# uc2950.net
KiCad netlist of a schematic drawn in EAGLE
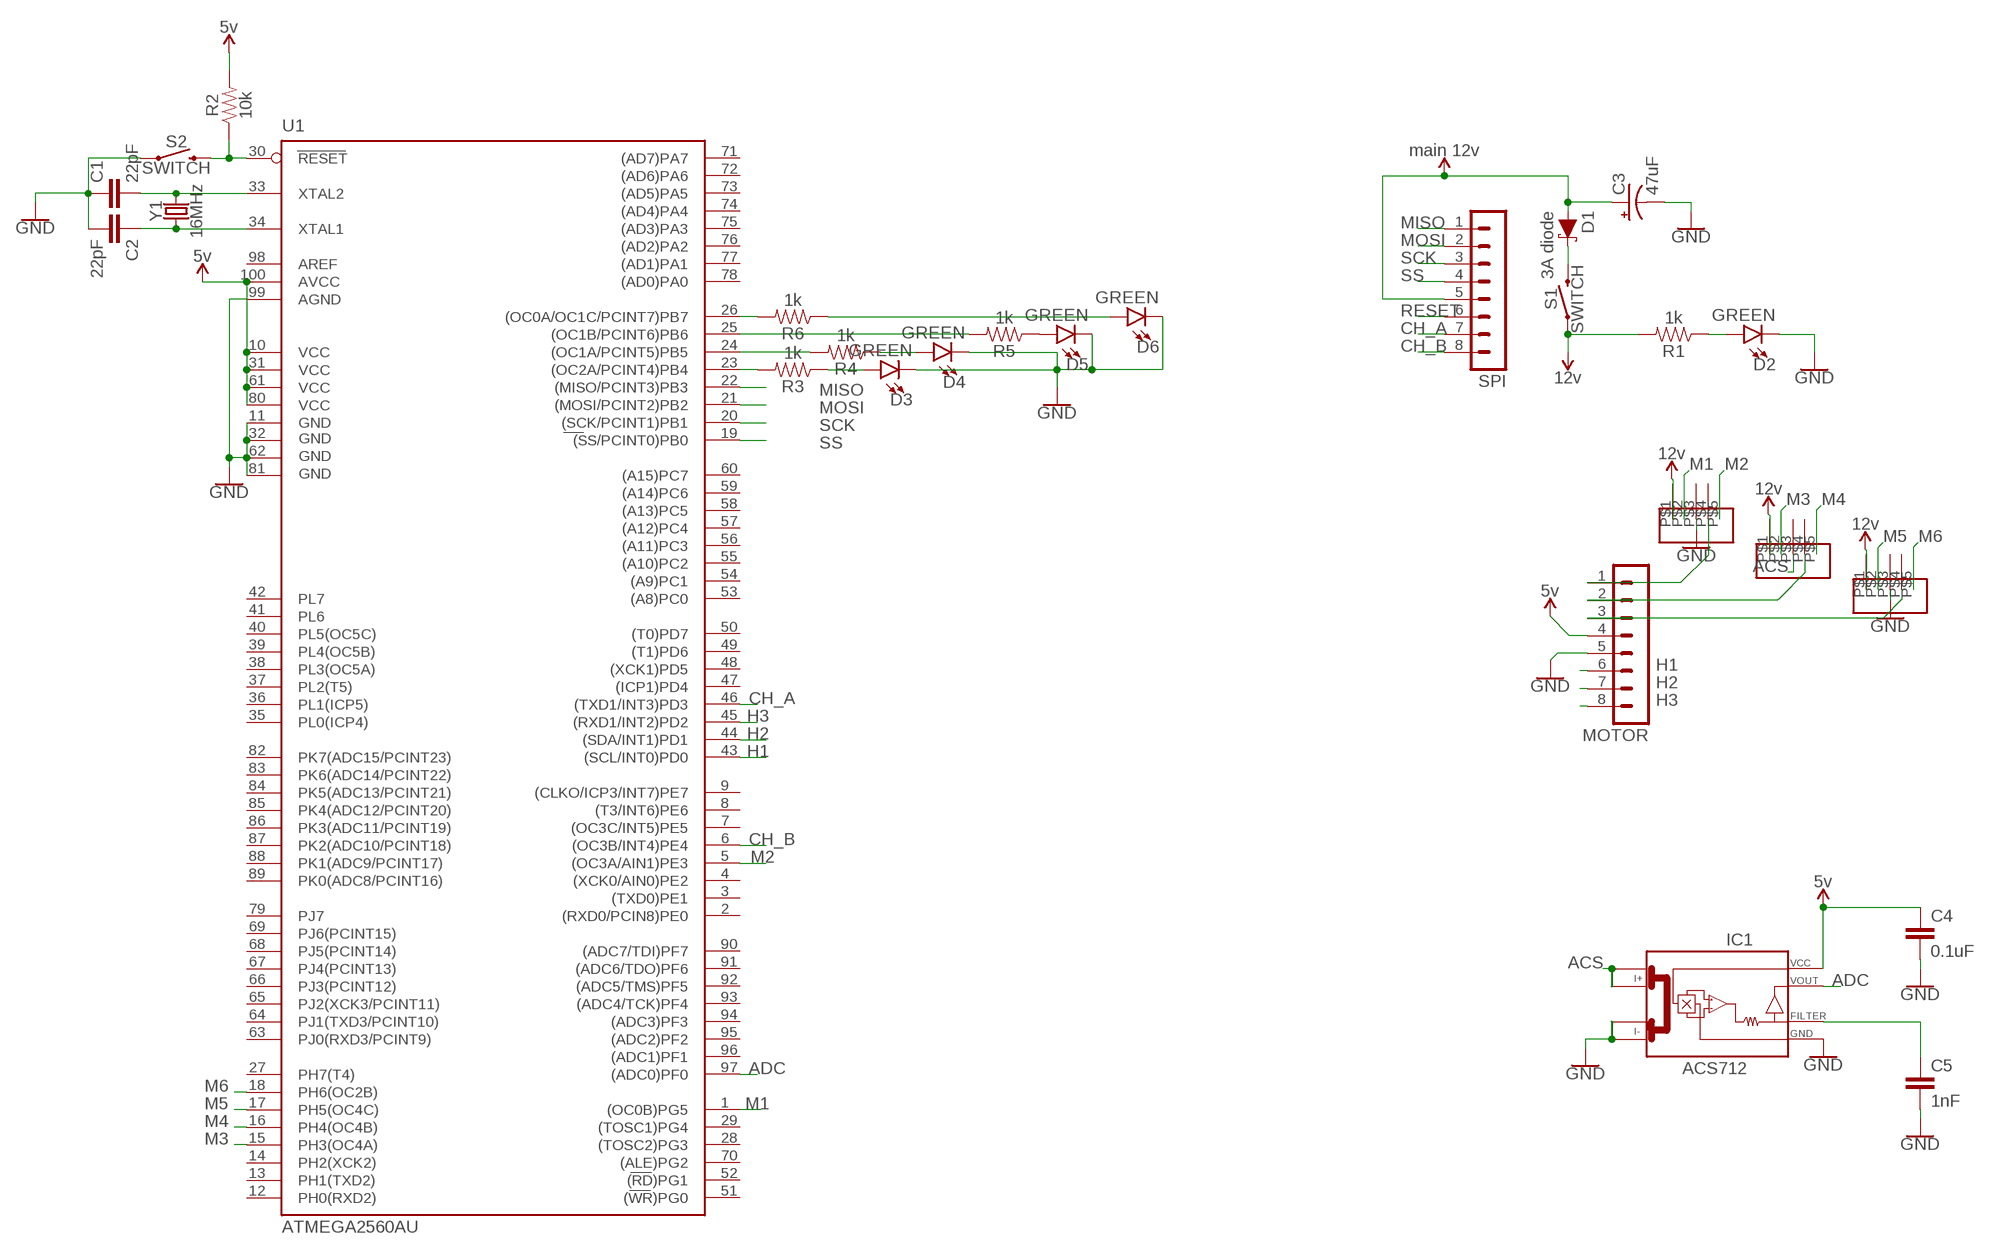
[diagram p0: schematic, sheet 1]

(export (version "E")
  (design (tool "Eeschema 10.0.6"))
  (components
    (comp (ref "C1")
      (value "22pF")
      (footprint "eagle-import:0603")
      (libsource (lib "eagle-import") (part "22PF-0603-50V-5%"))
    )
    (comp (ref "C2")
      (value "22pF")
      (footprint "eagle-import:0603")
      (libsource (lib "eagle-import") (part "22PF-0603-50V-5%"))
    )
    (comp (ref "C3")
      (value "47uF")
      (footprint "eagle-import:EIA3528")
      (libsource (lib "eagle-import") (part "47UF-POLAR-EIA3528-10V-10%"))
    )
    (comp (ref "C4")
      (value "0.1uF")
      (footprint "eagle-import:0603")
      (libsource (lib "eagle-import") (part "0.1UF-0603-25V-(+80/-20%)"))
    )
    (comp (ref "C5")
      (value "1nF")
      (footprint "eagle-import:0603")
      (libsource (lib "eagle-import") (part "1.0NF/1000PF-0603-50V-10%"))
    )
    (comp (ref "D1")
      (value "3A diode")
      (footprint "eagle-import:SMA-DIODE")
      (libsource (lib "eagle-import") (part "DIODE-SCHOTTKY-B340A"))
    )
    (comp (ref "D2")
      (value "GREEN")
      (footprint "eagle-import:LED-0603")
      (libsource (lib "eagle-import") (part "LED-GREEN0603"))
    )
    (comp (ref "D3")
      (value "GREEN")
      (footprint "eagle-import:LED-0603")
      (libsource (lib "eagle-import") (part "LED-GREEN0603"))
    )
    (comp (ref "D4")
      (value "GREEN")
      (footprint "eagle-import:LED-0603")
      (libsource (lib "eagle-import") (part "LED-GREEN0603"))
    )
    (comp (ref "D5")
      (value "GREEN")
      (footprint "eagle-import:LED-0603")
      (libsource (lib "eagle-import") (part "LED-GREEN0603"))
    )
    (comp (ref "D6")
      (value "GREEN")
      (footprint "eagle-import:LED-0603")
      (libsource (lib "eagle-import") (part "LED-GREEN0603"))
    )
    (comp (ref "IC1")
      (value "ACS712")
      (footprint "eagle-import:SO08")
      (libsource (lib "eagle-import") (part "ACS712"))
    )
    (comp (ref "M1")
      (value "M1")
      (footprint "eagle-import:UC2950")
      (libsource (lib "eagle-import") (part "UC2950"))
    )
    (comp (ref "M2")
      (value "M2")
      (footprint "eagle-import:UC2950")
      (libsource (lib "eagle-import") (part "UC2950"))
    )
    (comp (ref "M3")
      (value "M3")
      (footprint "eagle-import:UC2950")
      (libsource (lib "eagle-import") (part "UC2950"))
    )
    (comp (ref "MOTOR")
      (value "MA08-1")
      (footprint "eagle-import:MA08-1")
      (libsource (lib "eagle-import") (part "MA08-1"))
    )
    (comp (ref "R1")
      (value "1k")
      (footprint "eagle-import:0603")
      (libsource (lib "eagle-import") (part "1KOHM-0603-1/10W-1%"))
    )
    (comp (ref "R2")
      (value "10k")
      (footprint "eagle-import:0603")
      (libsource (lib "eagle-import") (part "10KOHM-0603-1/10W-1%"))
    )
    (comp (ref "R3")
      (value "1k")
      (footprint "eagle-import:0603")
      (libsource (lib "eagle-import") (part "1KOHM-0603-1/10W-1%"))
    )
    (comp (ref "R4")
      (value "1k")
      (footprint "eagle-import:0603")
      (libsource (lib "eagle-import") (part "1KOHM-0603-1/10W-1%"))
    )
    (comp (ref "R5")
      (value "1k")
      (footprint "eagle-import:0603")
      (libsource (lib "eagle-import") (part "1KOHM-0603-1/10W-1%"))
    )
    (comp (ref "R6")
      (value "1k")
      (footprint "eagle-import:0603")
      (libsource (lib "eagle-import") (part "1KOHM-0603-1/10W-1%"))
    )
    (comp (ref "S1")
      (value "SWITCH")
      (footprint "eagle-import:TACTILE_SWITCH_SMD_4.6X2.8MM")
      (libsource (lib "eagle-import") (part "MOMENTARY-SWITCH-SPST-SMD-4.6X2.8MM"))
    )
    (comp (ref "S2")
      (value "SWITCH")
      (footprint "eagle-import:TACTILE_SWITCH_SMD_4.6X2.8MM")
      (libsource (lib "eagle-import") (part "MOMENTARY-SWITCH-SPST-SMD-4.6X2.8MM"))
    )
    (comp (ref "SPI")
      (value "MA08-1")
      (footprint "eagle-import:MA08-1")
      (libsource (lib "eagle-import") (part "MA08-1"))
    )
    (comp (ref "U1")
      (value "ATMEGA2560AU")
      (footprint "eagle-import:TQFP100")
      (libsource (lib "eagle-import") (part "ATMEGA2560AU"))
    )
    (comp (ref "Y1")
      (value "16MHz")
      (footprint "eagle-import:CRYSTAL-SMD-5X3.2-4PAD")
      (libsource (lib "eagle-import") (part "CRYSTAL-16MHZSMD-5X3.2"))
    )
  )
  (nets
    (net (code "1") (name "/ACS") (class "Default")
      (node (ref "IC1") (pin "1") (pinfunction "I+_0_1") (pintype "bidirectional"))
      (node (ref "IC1") (pin "2") (pinfunction "I+_1_2") (pintype "bidirectional"))
      (node (ref "M2") (pin "P$3") (pinfunction "P$3_P$3") (pintype "bidirectional"))
    )
    (net (code "2") (name "/ADC") (class "Default")
      (node (ref "IC1") (pin "7") (pinfunction "VOUT_7") (pintype "output"))
      (node (ref "U1") (pin "97") (pinfunction "(ADC0)PF0_97") (pintype "bidirectional"))
    )
    (net (code "3") (name "/CH_A") (class "Default")
      (node (ref "SPI") (pin "7") (pinfunction "7_7") (pintype "passive"))
      (node (ref "U1") (pin "46") (pinfunction "(TXD1/INT3)PD3_46") (pintype "bidirectional"))
    )
    (net (code "4") (name "/CH_B") (class "Default")
      (node (ref "SPI") (pin "8") (pinfunction "8_8") (pintype "passive"))
      (node (ref "U1") (pin "6") (pinfunction "(OC3B/INT4)PE4_6") (pintype "bidirectional"))
    )
    (net (code "5") (name "/H1") (class "Default")
      (node (ref "MOTOR") (pin "6") (pinfunction "6_6") (pintype "passive"))
      (node (ref "U1") (pin "43") (pinfunction "(SCL/INT0)PD0_43") (pintype "bidirectional"))
    )
    (net (code "6") (name "/H2") (class "Default")
      (node (ref "MOTOR") (pin "7") (pinfunction "7_7") (pintype "passive"))
      (node (ref "U1") (pin "44") (pinfunction "(SDA/INT1)PD1_44") (pintype "bidirectional"))
    )
    (net (code "7") (name "/H3") (class "Default")
      (node (ref "MOTOR") (pin "8") (pinfunction "8_8") (pintype "passive"))
      (node (ref "U1") (pin "45") (pinfunction "(RXD1/INT2)PD2_45") (pintype "bidirectional"))
    )
    (net (code "8") (name "/M1") (class "Default")
      (node (ref "M1") (pin "P$2") (pinfunction "P$2_P$2") (pintype "bidirectional"))
      (node (ref "U1") (pin "1") (pinfunction "(OC0B)PG5_1") (pintype "bidirectional"))
    )
    (net (code "9") (name "/M2") (class "Default")
      (node (ref "M1") (pin "P$5") (pinfunction "P$5_P$5") (pintype "bidirectional"))
      (node (ref "U1") (pin "5") (pinfunction "(OC3A/AIN1)PE3_5") (pintype "bidirectional"))
    )
    (net (code "10") (name "/M3") (class "Default")
      (node (ref "M2") (pin "P$2") (pinfunction "P$2_P$2") (pintype "bidirectional"))
      (node (ref "U1") (pin "15") (pinfunction "PH3(OC4A)_15") (pintype "bidirectional"))
    )
    (net (code "11") (name "/M4") (class "Default")
      (node (ref "M2") (pin "P$5") (pinfunction "P$5_P$5") (pintype "bidirectional"))
      (node (ref "U1") (pin "16") (pinfunction "PH4(OC4B)_16") (pintype "bidirectional"))
    )
    (net (code "12") (name "/M5") (class "Default")
      (node (ref "M3") (pin "P$2") (pinfunction "P$2_P$2") (pintype "bidirectional"))
      (node (ref "U1") (pin "17") (pinfunction "PH5(OC4C)_17") (pintype "bidirectional"))
    )
    (net (code "13") (name "/M6") (class "Default")
      (node (ref "M3") (pin "P$5") (pinfunction "P$5_P$5") (pintype "bidirectional"))
      (node (ref "U1") (pin "18") (pinfunction "PH6(OC2B)_18") (pintype "bidirectional"))
    )
    (net (code "14") (name "/MISO") (class "Default")
      (node (ref "SPI") (pin "1") (pinfunction "1_1") (pintype "passive"))
      (node (ref "U1") (pin "22") (pinfunction "(MISO/PCINT3)PB3_22") (pintype "bidirectional"))
    )
    (net (code "15") (name "/MOSI") (class "Default")
      (node (ref "SPI") (pin "2") (pinfunction "2_2") (pintype "passive"))
      (node (ref "U1") (pin "21") (pinfunction "(MOSI/PCINT2)PB2_21") (pintype "bidirectional"))
    )
    (net (code "16") (name "/RESET") (class "Default")
      (node (ref "R2") (pin "1") (pinfunction "1_1") (pintype "passive"))
      (node (ref "S2") (pin "3") (pinfunction "2_3") (pintype "passive"))
      (node (ref "S2") (pin "4") (pinfunction "2_4") (pintype "passive"))
      (node (ref "SPI") (pin "6") (pinfunction "6_6") (pintype "passive"))
      (node (ref "U1") (pin "30") (pinfunction "RESET_30") (pintype "input"))
    )
    (net (code "17") (name "/SCK") (class "Default")
      (node (ref "SPI") (pin "3") (pinfunction "3_3") (pintype "passive"))
      (node (ref "U1") (pin "20") (pinfunction "(SCK/PCINT1)PB1_20") (pintype "bidirectional"))
    )
    (net (code "18") (name "/SS") (class "Default")
      (node (ref "SPI") (pin "4") (pinfunction "4_4") (pintype "passive"))
      (node (ref "U1") (pin "19") (pinfunction "(SS/PCINT0)PB0_19") (pintype "bidirectional"))
    )
    (net (code "19") (name "5v") (class "Default")
      (node (ref "C4") (pin "1") (pinfunction "1_1") (pintype "passive"))
      (node (ref "IC1") (pin "8") (pinfunction "VCC_8") (pintype "power_in"))
      (node (ref "MOTOR") (pin "4") (pinfunction "4_4") (pintype "passive"))
      (node (ref "R2") (pin "2") (pinfunction "2_2") (pintype "passive"))
      (node (ref "U1") (pin "10") (pinfunction "VCC_10") (pintype "power_in"))
      (node (ref "U1") (pin "100") (pinfunction "AVCC_100") (pintype "power_in"))
      (node (ref "U1") (pin "31") (pinfunction "VCC1_31") (pintype "power_in"))
      (node (ref "U1") (pin "61") (pinfunction "VCC2_61") (pintype "power_in"))
      (node (ref "U1") (pin "80") (pinfunction "VCC3_80") (pintype "power_in"))
    )
    (net (code "20") (name "12v") (class "Default")
      (node (ref "M1") (pin "P$1") (pinfunction "P$1_P$1") (pintype "bidirectional"))
      (node (ref "M2") (pin "P$1") (pinfunction "P$1_P$1") (pintype "bidirectional"))
      (node (ref "M3") (pin "P$1") (pinfunction "P$1_P$1") (pintype "bidirectional"))
      (node (ref "R1") (pin "2") (pinfunction "2_2") (pintype "passive"))
      (node (ref "S1") (pin "1") (pinfunction "1_1") (pintype "passive"))
      (node (ref "S1") (pin "2") (pinfunction "1_2") (pintype "passive"))
    )
    (net (code "21") (name "GND") (class "Default")
      (node (ref "C1") (pin "1") (pinfunction "1_1") (pintype "passive"))
      (node (ref "C2") (pin "2") (pinfunction "2_2") (pintype "passive"))
      (node (ref "C3") (pin "C") (pinfunction "-_C") (pintype "passive"))
      (node (ref "C4") (pin "2") (pinfunction "2_2") (pintype "passive"))
      (node (ref "C5") (pin "2") (pinfunction "2_2") (pintype "passive"))
      (node (ref "D2") (pin "C") (pinfunction "C_C") (pintype "passive"))
      (node (ref "D3") (pin "C") (pinfunction "C_C") (pintype "passive"))
      (node (ref "D4") (pin "C") (pinfunction "C_C") (pintype "passive"))
      (node (ref "D5") (pin "C") (pinfunction "C_C") (pintype "passive"))
      (node (ref "D6") (pin "C") (pinfunction "C_C") (pintype "passive"))
      (node (ref "IC1") (pin "3") (pinfunction "I-_0_3") (pintype "bidirectional"))
      (node (ref "IC1") (pin "4") (pinfunction "I-_1_4") (pintype "bidirectional"))
      (node (ref "IC1") (pin "5") (pinfunction "GND_5") (pintype "power_in"))
      (node (ref "M1") (pin "P$3") (pinfunction "P$3_P$3") (pintype "bidirectional"))
      (node (ref "M3") (pin "P$3") (pinfunction "P$3_P$3") (pintype "bidirectional"))
      (node (ref "MOTOR") (pin "5") (pinfunction "5_5") (pintype "passive"))
      (node (ref "S2") (pin "1") (pinfunction "1_1") (pintype "passive"))
      (node (ref "S2") (pin "2") (pinfunction "1_2") (pintype "passive"))
      (node (ref "U1") (pin "11") (pinfunction "GND_11") (pintype "power_in"))
      (node (ref "U1") (pin "32") (pinfunction "GND1_32") (pintype "power_in"))
      (node (ref "U1") (pin "62") (pinfunction "GND2_62") (pintype "power_in"))
      (node (ref "U1") (pin "81") (pinfunction "GND3_81") (pintype "power_in"))
      (node (ref "U1") (pin "99") (pinfunction "AGND_99") (pintype "power_in"))
    )
    (net (code "22") (name "Net-(D1-PadC)") (class "Default")
      (node (ref "D1") (pin "C") (pinfunction "C_C") (pintype "passive"))
      (node (ref "S1") (pin "3") (pinfunction "2_3") (pintype "passive"))
      (node (ref "S1") (pin "4") (pinfunction "2_4") (pintype "passive"))
    )
    (net (code "23") (name "Net-(D2-PadA)") (class "Default")
      (node (ref "D2") (pin "A") (pinfunction "A_A") (pintype "passive"))
      (node (ref "R1") (pin "1") (pinfunction "1_1") (pintype "passive"))
    )
    (net (code "24") (name "Net-(D3-PadA)") (class "Default")
      (node (ref "D3") (pin "A") (pinfunction "A_A") (pintype "passive"))
      (node (ref "R3") (pin "1") (pinfunction "1_1") (pintype "passive"))
    )
    (net (code "25") (name "Net-(D4-PadA)") (class "Default")
      (node (ref "D4") (pin "A") (pinfunction "A_A") (pintype "passive"))
      (node (ref "R4") (pin "1") (pinfunction "1_1") (pintype "passive"))
    )
    (net (code "26") (name "Net-(D5-PadA)") (class "Default")
      (node (ref "D5") (pin "A") (pinfunction "A_A") (pintype "passive"))
      (node (ref "R5") (pin "1") (pinfunction "1_1") (pintype "passive"))
    )
    (net (code "27") (name "Net-(D6-PadA)") (class "Default")
      (node (ref "D6") (pin "A") (pinfunction "A_A") (pintype "passive"))
      (node (ref "R6") (pin "1") (pinfunction "1_1") (pintype "passive"))
    )
    (net (code "28") (name "Net-(IC1-FILTER)") (class "Default")
      (node (ref "C5") (pin "1") (pinfunction "1_1") (pintype "passive"))
      (node (ref "IC1") (pin "6") (pinfunction "FILTER_6") (pintype "bidirectional"))
    )
    (net (code "29") (name "Net-(M1-PadP$4)") (class "Default")
      (node (ref "M1") (pin "P$4") (pinfunction "P$4_P$4") (pintype "bidirectional"))
      (node (ref "MOTOR") (pin "1") (pinfunction "1_1") (pintype "passive"))
    )
    (net (code "30") (name "Net-(M2-PadP$4)") (class "Default")
      (node (ref "M2") (pin "P$4") (pinfunction "P$4_P$4") (pintype "bidirectional"))
      (node (ref "MOTOR") (pin "2") (pinfunction "2_2") (pintype "passive"))
    )
    (net (code "31") (name "Net-(M3-PadP$4)") (class "Default")
      (node (ref "M3") (pin "P$4") (pinfunction "P$4_P$4") (pintype "bidirectional"))
      (node (ref "MOTOR") (pin "3") (pinfunction "3_3") (pintype "passive"))
    )
    (net (code "32") (name "Net-(U1-(OC0A{slash}OC1C{slash}PCINT7)PB7)") (class "Default")
      (node (ref "R6") (pin "2") (pinfunction "2_2") (pintype "passive"))
      (node (ref "U1") (pin "26") (pinfunction "(OC0A/OC1C/PCINT7)PB7_26") (pintype "bidirectional"))
    )
    (net (code "33") (name "Net-(U1-(OC1A{slash}PCINT5)PB5)") (class "Default")
      (node (ref "R4") (pin "2") (pinfunction "2_2") (pintype "passive"))
      (node (ref "U1") (pin "24") (pinfunction "(OC1A/PCINT5)PB5_24") (pintype "bidirectional"))
    )
    (net (code "34") (name "Net-(U1-(OC1B{slash}PCINT6)PB6)") (class "Default")
      (node (ref "R5") (pin "2") (pinfunction "2_2") (pintype "passive"))
      (node (ref "U1") (pin "25") (pinfunction "(OC1B/PCINT6)PB6_25") (pintype "bidirectional"))
    )
    (net (code "35") (name "Net-(U1-(OC2A{slash}PCINT4)PB4)") (class "Default")
      (node (ref "R3") (pin "2") (pinfunction "2_2") (pintype "passive"))
      (node (ref "U1") (pin "23") (pinfunction "(OC2A/PCINT4)PB4_23") (pintype "bidirectional"))
    )
    (net (code "36") (name "Net-(U1-XTAL1)") (class "Default")
      (node (ref "C2") (pin "1") (pinfunction "1_1") (pintype "passive"))
      (node (ref "U1") (pin "34") (pinfunction "XTAL1_34") (pintype "input"))
      (node (ref "Y1") (pin "1") (pinfunction "1_1") (pintype "passive"))
    )
    (net (code "37") (name "Net-(U1-XTAL2)") (class "Default")
      (node (ref "C1") (pin "2") (pinfunction "2_2") (pintype "passive"))
      (node (ref "U1") (pin "33") (pinfunction "XTAL2_33") (pintype "output"))
      (node (ref "Y1") (pin "3") (pinfunction "2_3") (pintype "passive"))
    )
    (net (code "38") (name "main 12v") (class "Default")
      (node (ref "C3") (pin "A") (pinfunction "+_A") (pintype "passive"))
      (node (ref "D1") (pin "A") (pinfunction "A_A") (pintype "passive"))
      (node (ref "SPI") (pin "5") (pinfunction "5_5") (pintype "passive"))
    )
    (net (code "39") (name "unconnected-(U1-(A8)PC0-Pad53)") (class "Default")
      (node (ref "U1") (pin "53") (pinfunction "(A8)PC0_53") (pintype "bidirectional"))
    )
    (net (code "40") (name "unconnected-(U1-(A9)PC1-Pad54)") (class "Default")
      (node (ref "U1") (pin "54") (pinfunction "(A9)PC1_54") (pintype "bidirectional"))
    )
    (net (code "41") (name "unconnected-(U1-(A10)PC2-Pad55)") (class "Default")
      (node (ref "U1") (pin "55") (pinfunction "(A10)PC2_55") (pintype "bidirectional"))
    )
    (net (code "42") (name "unconnected-(U1-(A11)PC3-Pad56)") (class "Default")
      (node (ref "U1") (pin "56") (pinfunction "(A11)PC3_56") (pintype "bidirectional"))
    )
    (net (code "43") (name "unconnected-(U1-(A12)PC4-Pad57)") (class "Default")
      (node (ref "U1") (pin "57") (pinfunction "(A12)PC4_57") (pintype "bidirectional"))
    )
    (net (code "44") (name "unconnected-(U1-(A13)PC5-Pad58)") (class "Default")
      (node (ref "U1") (pin "58") (pinfunction "(A13)PC5_58") (pintype "bidirectional"))
    )
    (net (code "45") (name "unconnected-(U1-(A14)PC6-Pad59)") (class "Default")
      (node (ref "U1") (pin "59") (pinfunction "(A14)PC6_59") (pintype "bidirectional"))
    )
    (net (code "46") (name "unconnected-(U1-(A15)PC7-Pad60)") (class "Default")
      (node (ref "U1") (pin "60") (pinfunction "(A15)PC7_60") (pintype "bidirectional"))
    )
    (net (code "47") (name "unconnected-(U1-(AD0)PA0-Pad78)") (class "Default")
      (node (ref "U1") (pin "78") (pinfunction "(AD0)PA0_78") (pintype "bidirectional"))
    )
    (net (code "48") (name "unconnected-(U1-(AD1)PA1-Pad77)") (class "Default")
      (node (ref "U1") (pin "77") (pinfunction "(AD1)PA1_77") (pintype "bidirectional"))
    )
    (net (code "49") (name "unconnected-(U1-(AD2)PA2-Pad76)") (class "Default")
      (node (ref "U1") (pin "76") (pinfunction "(AD2)PA2_76") (pintype "bidirectional"))
    )
    (net (code "50") (name "unconnected-(U1-(AD3)PA3-Pad75)") (class "Default")
      (node (ref "U1") (pin "75") (pinfunction "(AD3)PA3_75") (pintype "bidirectional"))
    )
    (net (code "51") (name "unconnected-(U1-(AD4)PA4-Pad74)") (class "Default")
      (node (ref "U1") (pin "74") (pinfunction "(AD4)PA4_74") (pintype "bidirectional"))
    )
    (net (code "52") (name "unconnected-(U1-(AD5)PA5-Pad73)") (class "Default")
      (node (ref "U1") (pin "73") (pinfunction "(AD5)PA5_73") (pintype "bidirectional"))
    )
    (net (code "53") (name "unconnected-(U1-(AD6)PA6-Pad72)") (class "Default")
      (node (ref "U1") (pin "72") (pinfunction "(AD6)PA6_72") (pintype "bidirectional"))
    )
    (net (code "54") (name "unconnected-(U1-(AD7)PA7-Pad71)") (class "Default")
      (node (ref "U1") (pin "71") (pinfunction "(AD7)PA7_71") (pintype "bidirectional"))
    )
    (net (code "55") (name "unconnected-(U1-(ADC1)PF1-Pad96)") (class "Default")
      (node (ref "U1") (pin "96") (pinfunction "(ADC1)PF1_96") (pintype "bidirectional"))
    )
    (net (code "56") (name "unconnected-(U1-(ADC2)PF2-Pad95)") (class "Default")
      (node (ref "U1") (pin "95") (pinfunction "(ADC2)PF2_95") (pintype "bidirectional"))
    )
    (net (code "57") (name "unconnected-(U1-(ADC3)PF3-Pad94)") (class "Default")
      (node (ref "U1") (pin "94") (pinfunction "(ADC3)PF3_94") (pintype "bidirectional"))
    )
    (net (code "58") (name "unconnected-(U1-(ADC4{slash}TCK)PF4-Pad93)") (class "Default")
      (node (ref "U1") (pin "93") (pinfunction "(ADC4/TCK)PF4_93") (pintype "bidirectional"))
    )
    (net (code "59") (name "unconnected-(U1-(ADC5{slash}TMS)PF5-Pad92)") (class "Default")
      (node (ref "U1") (pin "92") (pinfunction "(ADC5/TMS)PF5_92") (pintype "bidirectional"))
    )
    (net (code "60") (name "unconnected-(U1-(ADC6{slash}TDO)PF6-Pad91)") (class "Default")
      (node (ref "U1") (pin "91") (pinfunction "(ADC6/TDO)PF6_91") (pintype "bidirectional"))
    )
    (net (code "61") (name "unconnected-(U1-(ADC7{slash}TDI)PF7-Pad90)") (class "Default")
      (node (ref "U1") (pin "90") (pinfunction "(ADC7/TDI)PF7_90") (pintype "bidirectional"))
    )
    (net (code "62") (name "unconnected-(U1-(ALE)PG2-Pad70)") (class "Default")
      (node (ref "U1") (pin "70") (pinfunction "(ALE)PG2_70") (pintype "bidirectional"))
    )
    (net (code "63") (name "unconnected-(U1-(CLKO{slash}ICP3{slash}INT7)PE7-Pad9)") (class "Default")
      (node (ref "U1") (pin "9") (pinfunction "(CLKO/ICP3/INT7)PE7_9") (pintype "bidirectional"))
    )
    (net (code "64") (name "unconnected-(U1-(ICP1)PD4-Pad47)") (class "Default")
      (node (ref "U1") (pin "47") (pinfunction "(ICP1)PD4_47") (pintype "bidirectional"))
    )
    (net (code "65") (name "unconnected-(U1-(OC3C{slash}INT5)PE5-Pad7)") (class "Default")
      (node (ref "U1") (pin "7") (pinfunction "(OC3C/INT5)PE5_7") (pintype "bidirectional"))
    )
    (net (code "66") (name "unconnected-(U1-(RD)PG1-Pad52)") (class "Default")
      (node (ref "U1") (pin "52") (pinfunction "(RD)PG1_52") (pintype "bidirectional"))
    )
    (net (code "67") (name "unconnected-(U1-(RXD0{slash}PCIN8)PE0-Pad2)") (class "Default")
      (node (ref "U1") (pin "2") (pinfunction "(RXD0/PCIN8)PE0_2") (pintype "bidirectional"))
    )
    (net (code "68") (name "unconnected-(U1-(T0)PD7-Pad50)") (class "Default")
      (node (ref "U1") (pin "50") (pinfunction "(T0)PD7_50") (pintype "bidirectional"))
    )
    (net (code "69") (name "unconnected-(U1-(T1)PD6-Pad49)") (class "Default")
      (node (ref "U1") (pin "49") (pinfunction "(T1)PD6_49") (pintype "bidirectional"))
    )
    (net (code "70") (name "unconnected-(U1-(T3{slash}INT6)PE6-Pad8)") (class "Default")
      (node (ref "U1") (pin "8") (pinfunction "(T3/INT6)PE6_8") (pintype "bidirectional"))
    )
    (net (code "71") (name "unconnected-(U1-(TOSC1)PG4-Pad29)") (class "Default")
      (node (ref "U1") (pin "29") (pinfunction "(TOSC1)PG4_29") (pintype "bidirectional"))
    )
    (net (code "72") (name "unconnected-(U1-(TOSC2)PG3-Pad28)") (class "Default")
      (node (ref "U1") (pin "28") (pinfunction "(TOSC2)PG3_28") (pintype "bidirectional"))
    )
    (net (code "73") (name "unconnected-(U1-(TXD0)PE1-Pad3)") (class "Default")
      (node (ref "U1") (pin "3") (pinfunction "(TXD0)PE1_3") (pintype "bidirectional"))
    )
    (net (code "74") (name "unconnected-(U1-(WR)PG0-Pad51)") (class "Default")
      (node (ref "U1") (pin "51") (pinfunction "(WR)PG0_51") (pintype "bidirectional"))
    )
    (net (code "75") (name "unconnected-(U1-(XCK0{slash}AIN0)PE2-Pad4)") (class "Default")
      (node (ref "U1") (pin "4") (pinfunction "(XCK0/AIN0)PE2_4") (pintype "bidirectional"))
    )
    (net (code "76") (name "unconnected-(U1-(XCK1)PD5-Pad48)") (class "Default")
      (node (ref "U1") (pin "48") (pinfunction "(XCK1)PD5_48") (pintype "bidirectional"))
    )
    (net (code "77") (name "unconnected-(U1-AREF-Pad98)") (class "Default")
      (node (ref "U1") (pin "98") (pinfunction "AREF_98") (pintype "bidirectional"))
    )
    (net (code "78") (name "unconnected-(U1-PH0(RXD2)-Pad12)") (class "Default")
      (node (ref "U1") (pin "12") (pinfunction "PH0(RXD2)_12") (pintype "bidirectional"))
    )
    (net (code "79") (name "unconnected-(U1-PH1(TXD2)-Pad13)") (class "Default")
      (node (ref "U1") (pin "13") (pinfunction "PH1(TXD2)_13") (pintype "bidirectional"))
    )
    (net (code "80") (name "unconnected-(U1-PH2(XCK2)-Pad14)") (class "Default")
      (node (ref "U1") (pin "14") (pinfunction "PH2(XCK2)_14") (pintype "bidirectional"))
    )
    (net (code "81") (name "unconnected-(U1-PH7(T4)-Pad27)") (class "Default")
      (node (ref "U1") (pin "27") (pinfunction "PH7(T4)_27") (pintype "bidirectional"))
    )
    (net (code "82") (name "unconnected-(U1-PJ0(RXD3{slash}PCINT9)-Pad63)") (class "Default")
      (node (ref "U1") (pin "63") (pinfunction "PJ0(RXD3/PCINT9)_63") (pintype "bidirectional"))
    )
    (net (code "83") (name "unconnected-(U1-PJ1(TXD3{slash}PCINT10)-Pad64)") (class "Default")
      (node (ref "U1") (pin "64") (pinfunction "PJ1(TXD3/PCINT10)_64") (pintype "bidirectional"))
    )
    (net (code "84") (name "unconnected-(U1-PJ2(XCK3{slash}PCINT11)-Pad65)") (class "Default")
      (node (ref "U1") (pin "65") (pinfunction "PJ2(XCK3/PCINT11)_65") (pintype "bidirectional"))
    )
    (net (code "85") (name "unconnected-(U1-PJ3(PCINT12)-Pad66)") (class "Default")
      (node (ref "U1") (pin "66") (pinfunction "PJ3(PCINT12)_66") (pintype "bidirectional"))
    )
    (net (code "86") (name "unconnected-(U1-PJ4(PCINT13)-Pad67)") (class "Default")
      (node (ref "U1") (pin "67") (pinfunction "PJ4(PCINT13)_67") (pintype "bidirectional"))
    )
    (net (code "87") (name "unconnected-(U1-PJ5(PCINT14)-Pad68)") (class "Default")
      (node (ref "U1") (pin "68") (pinfunction "PJ5(PCINT14)_68") (pintype "bidirectional"))
    )
    (net (code "88") (name "unconnected-(U1-PJ6(PCINT15)-Pad69)") (class "Default")
      (node (ref "U1") (pin "69") (pinfunction "PJ6(PCINT15)_69") (pintype "bidirectional"))
    )
    (net (code "89") (name "unconnected-(U1-PJ7-Pad79)") (class "Default")
      (node (ref "U1") (pin "79") (pinfunction "PJ7_79") (pintype "bidirectional"))
    )
    (net (code "90") (name "unconnected-(U1-PK0(ADC8{slash}PCINT16)-Pad89)") (class "Default")
      (node (ref "U1") (pin "89") (pinfunction "PK0(ADC8/PCINT16)_89") (pintype "bidirectional"))
    )
    (net (code "91") (name "unconnected-(U1-PK1(ADC9{slash}PCINT17)-Pad88)") (class "Default")
      (node (ref "U1") (pin "88") (pinfunction "PK1(ADC9/PCINT17)_88") (pintype "bidirectional"))
    )
    (net (code "92") (name "unconnected-(U1-PK2(ADC10{slash}PCINT18)-Pad87)") (class "Default")
      (node (ref "U1") (pin "87") (pinfunction "PK2(ADC10/PCINT18)_87") (pintype "bidirectional"))
    )
    (net (code "93") (name "unconnected-(U1-PK3(ADC11{slash}PCINT19)-Pad86)") (class "Default")
      (node (ref "U1") (pin "86") (pinfunction "PK3(ADC11/PCINT19)_86") (pintype "bidirectional"))
    )
    (net (code "94") (name "unconnected-(U1-PK4(ADC12{slash}PCINT20)-Pad85)") (class "Default")
      (node (ref "U1") (pin "85") (pinfunction "PK4(ADC12/PCINT20)_85") (pintype "bidirectional"))
    )
    (net (code "95") (name "unconnected-(U1-PK5(ADC13{slash}PCINT21)-Pad84)") (class "Default")
      (node (ref "U1") (pin "84") (pinfunction "PK5(ADC13/PCINT21)_84") (pintype "bidirectional"))
    )
    (net (code "96") (name "unconnected-(U1-PK6(ADC14{slash}PCINT22)-Pad83)") (class "Default")
      (node (ref "U1") (pin "83") (pinfunction "PK6(ADC14/PCINT22)_83") (pintype "bidirectional"))
    )
    (net (code "97") (name "unconnected-(U1-PK7(ADC15{slash}PCINT23)-Pad82)") (class "Default")
      (node (ref "U1") (pin "82") (pinfunction "PK7(ADC15/PCINT23)_82") (pintype "bidirectional"))
    )
    (net (code "98") (name "unconnected-(U1-PL0(ICP4)-Pad35)") (class "Default")
      (node (ref "U1") (pin "35") (pinfunction "PL0(ICP4)_35") (pintype "bidirectional"))
    )
    (net (code "99") (name "unconnected-(U1-PL1(ICP5)-Pad36)") (class "Default")
      (node (ref "U1") (pin "36") (pinfunction "PL1(ICP5)_36") (pintype "bidirectional"))
    )
    (net (code "100") (name "unconnected-(U1-PL2(T5)-Pad37)") (class "Default")
      (node (ref "U1") (pin "37") (pinfunction "PL2(T5)_37") (pintype "bidirectional"))
    )
    (net (code "101") (name "unconnected-(U1-PL3(OC5A)-Pad38)") (class "Default")
      (node (ref "U1") (pin "38") (pinfunction "PL3(OC5A)_38") (pintype "bidirectional"))
    )
    (net (code "102") (name "unconnected-(U1-PL4(OC5B)-Pad39)") (class "Default")
      (node (ref "U1") (pin "39") (pinfunction "PL4(OC5B)_39") (pintype "bidirectional"))
    )
    (net (code "103") (name "unconnected-(U1-PL5(OC5C)-Pad40)") (class "Default")
      (node (ref "U1") (pin "40") (pinfunction "PL5(OC5C)_40") (pintype "bidirectional"))
    )
    (net (code "104") (name "unconnected-(U1-PL6-Pad41)") (class "Default")
      (node (ref "U1") (pin "41") (pinfunction "PL6_41") (pintype "bidirectional"))
    )
    (net (code "105") (name "unconnected-(U1-PL7-Pad42)") (class "Default")
      (node (ref "U1") (pin "42") (pinfunction "PL7_42") (pintype "bidirectional"))
    )
  )
)
